# tweite.net
KiCad netlist of a schematic drawn in EAGLE
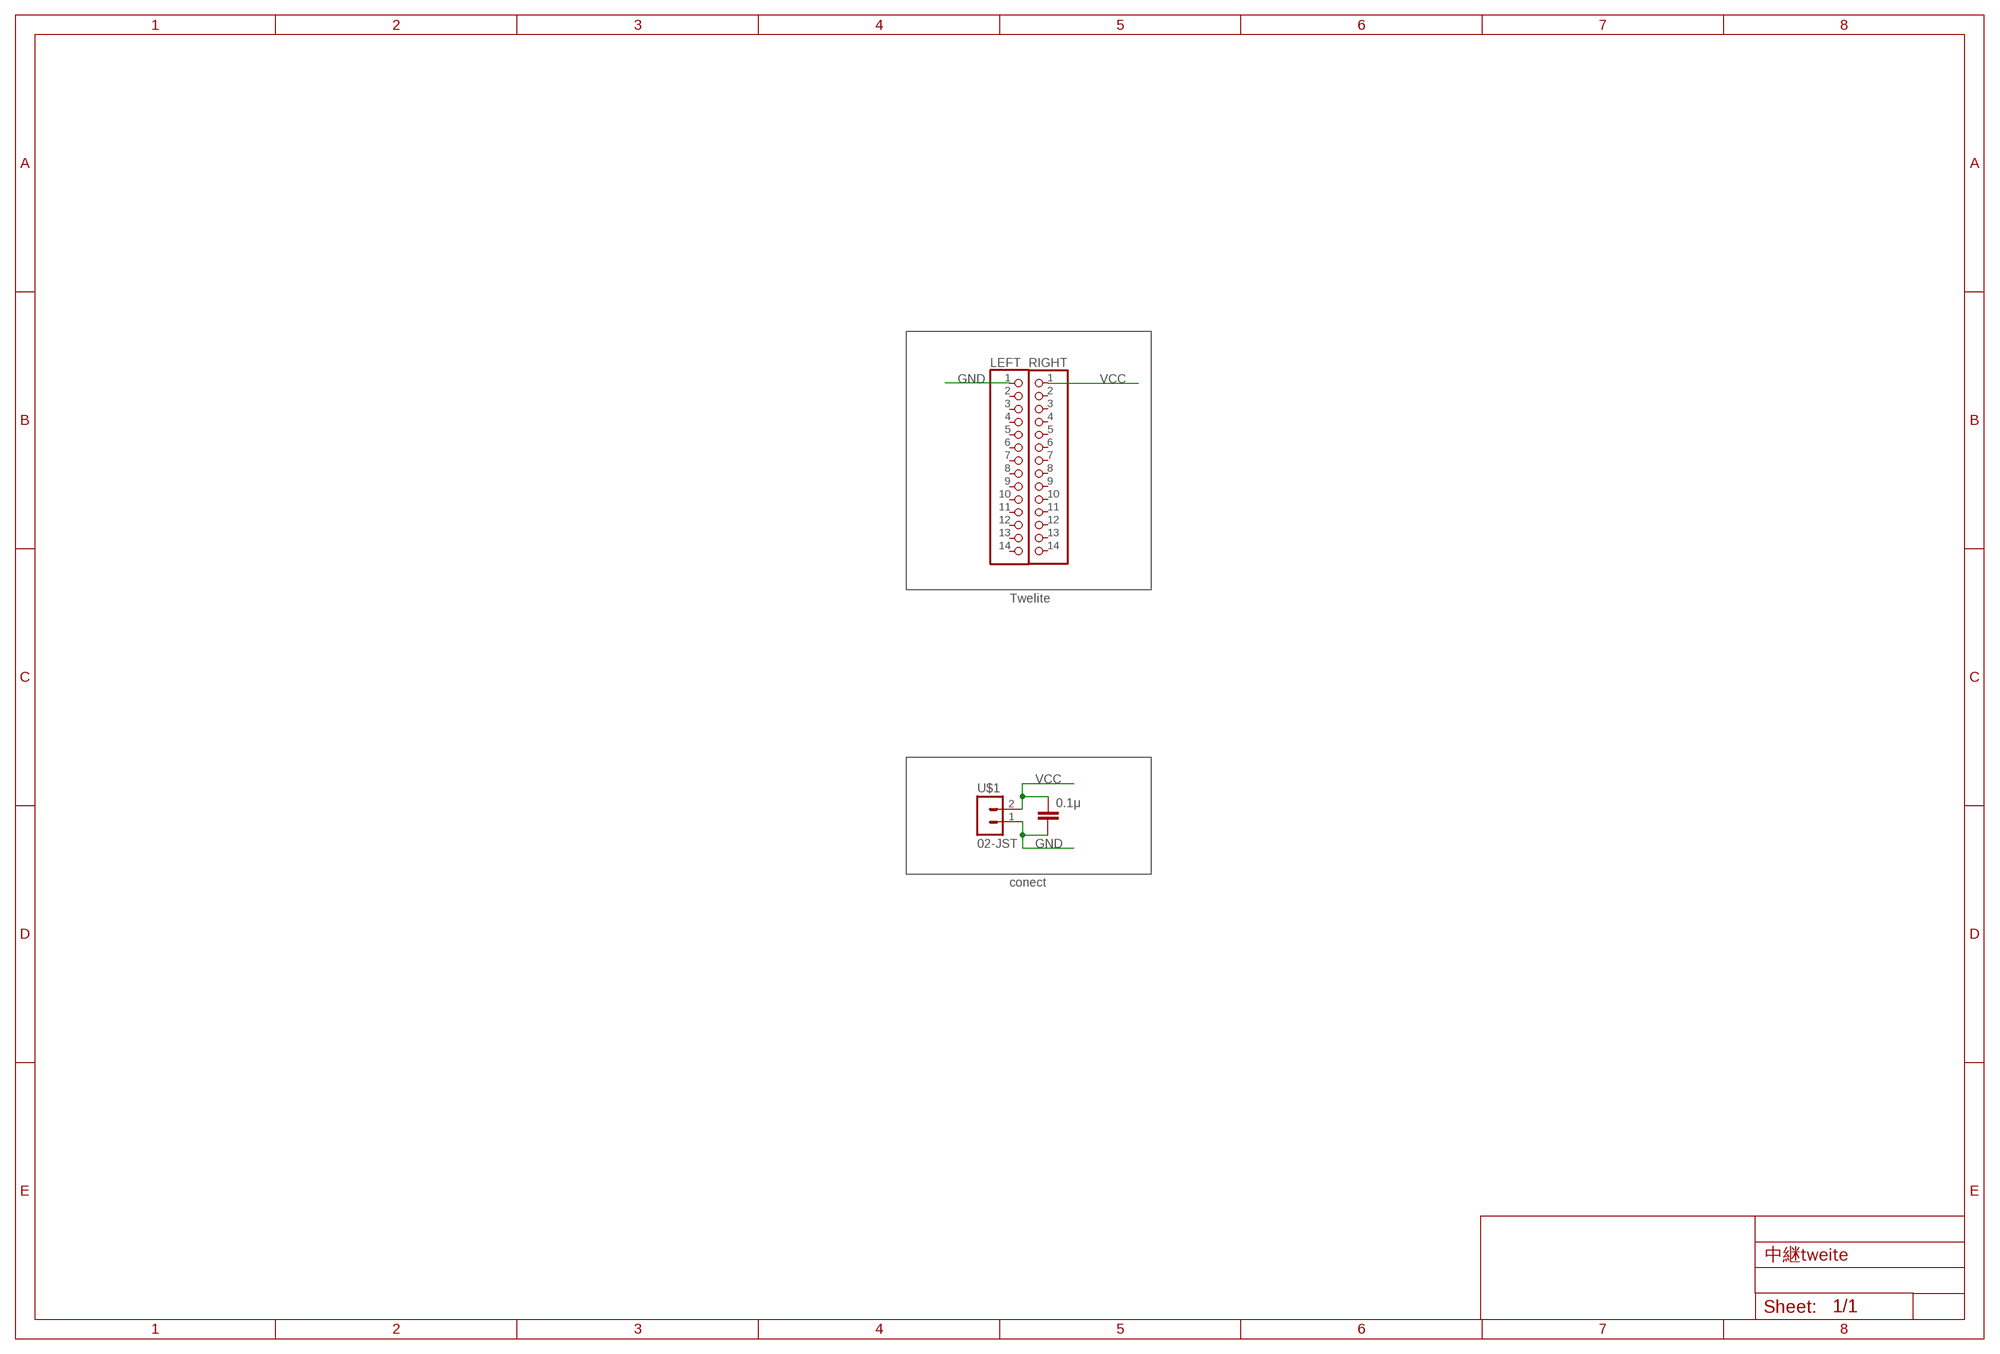
[diagram p0: schematic, sheet 1]

(export (version "E")
  (design (tool "Eeschema 10.0.6"))
  (components
    (comp (ref "0.1μ")
      (value "C-EU025-024X044")
      (footprint "eagle-import:C025-024X044")
      (libsource (lib "eagle-import") (part "C-EU025-024X044"))
    )
    (comp (ref "LEFT")
      (value "PINHD-1X14")
      (footprint "eagle-import:1X14")
      (libsource (lib "eagle-import") (part "PINHD-1X14"))
    )
    (comp (ref "RIGHT")
      (value "PINHD-1X14")
      (footprint "eagle-import:1X14")
      (libsource (lib "eagle-import") (part "PINHD-1X14"))
    )
    (comp (ref "U$1")
      (value "02-JST")
      (footprint "eagle-import:B2B-XH")
      (libsource (lib "eagle-import") (part "02-JST"))
    )
  )
  (nets
    (net (code "1") (name "/GND") (class "Default")
      (node (ref "0.1μ") (pin "2") (pinfunction "2_2") (pintype "passive"))
      (node (ref "LEFT") (pin "1") (pinfunction "1_1") (pintype "passive"))
      (node (ref "U$1") (pin "1") (pinfunction "1_1") (pintype "passive"))
    )
    (net (code "2") (name "/VCC") (class "Default")
      (node (ref "0.1μ") (pin "1") (pinfunction "1_1") (pintype "passive"))
      (node (ref "RIGHT") (pin "1") (pinfunction "1_1") (pintype "passive"))
      (node (ref "U$1") (pin "2") (pinfunction "2_2") (pintype "passive"))
    )
    (net (code "3") (name "unconnected-(LEFT-Pad2)") (class "Default")
      (node (ref "LEFT") (pin "2") (pinfunction "2_2") (pintype "passive"))
    )
    (net (code "4") (name "unconnected-(LEFT-Pad3)") (class "Default")
      (node (ref "LEFT") (pin "3") (pinfunction "3_3") (pintype "passive"))
    )
    (net (code "5") (name "unconnected-(LEFT-Pad4)") (class "Default")
      (node (ref "LEFT") (pin "4") (pinfunction "4_4") (pintype "passive"))
    )
    (net (code "6") (name "unconnected-(LEFT-Pad5)") (class "Default")
      (node (ref "LEFT") (pin "5") (pinfunction "5_5") (pintype "passive"))
    )
    (net (code "7") (name "unconnected-(LEFT-Pad6)") (class "Default")
      (node (ref "LEFT") (pin "6") (pinfunction "6_6") (pintype "passive"))
    )
    (net (code "8") (name "unconnected-(LEFT-Pad7)") (class "Default")
      (node (ref "LEFT") (pin "7") (pinfunction "7_7") (pintype "passive"))
    )
    (net (code "9") (name "unconnected-(LEFT-Pad8)") (class "Default")
      (node (ref "LEFT") (pin "8") (pinfunction "8_8") (pintype "passive"))
    )
    (net (code "10") (name "unconnected-(LEFT-Pad9)") (class "Default")
      (node (ref "LEFT") (pin "9") (pinfunction "9_9") (pintype "passive"))
    )
    (net (code "11") (name "unconnected-(LEFT-Pad10)") (class "Default")
      (node (ref "LEFT") (pin "10") (pinfunction "10_10") (pintype "passive"))
    )
    (net (code "12") (name "unconnected-(LEFT-Pad11)") (class "Default")
      (node (ref "LEFT") (pin "11") (pinfunction "11_11") (pintype "passive"))
    )
    (net (code "13") (name "unconnected-(LEFT-Pad12)") (class "Default")
      (node (ref "LEFT") (pin "12") (pinfunction "12_12") (pintype "passive"))
    )
    (net (code "14") (name "unconnected-(LEFT-Pad13)") (class "Default")
      (node (ref "LEFT") (pin "13") (pinfunction "13_13") (pintype "passive"))
    )
    (net (code "15") (name "unconnected-(LEFT-Pad14)") (class "Default")
      (node (ref "LEFT") (pin "14") (pinfunction "14_14") (pintype "passive"))
    )
    (net (code "16") (name "unconnected-(RIGHT-Pad2)") (class "Default")
      (node (ref "RIGHT") (pin "2") (pinfunction "2_2") (pintype "passive"))
    )
    (net (code "17") (name "unconnected-(RIGHT-Pad3)") (class "Default")
      (node (ref "RIGHT") (pin "3") (pinfunction "3_3") (pintype "passive"))
    )
    (net (code "18") (name "unconnected-(RIGHT-Pad4)") (class "Default")
      (node (ref "RIGHT") (pin "4") (pinfunction "4_4") (pintype "passive"))
    )
    (net (code "19") (name "unconnected-(RIGHT-Pad5)") (class "Default")
      (node (ref "RIGHT") (pin "5") (pinfunction "5_5") (pintype "passive"))
    )
    (net (code "20") (name "unconnected-(RIGHT-Pad6)") (class "Default")
      (node (ref "RIGHT") (pin "6") (pinfunction "6_6") (pintype "passive"))
    )
    (net (code "21") (name "unconnected-(RIGHT-Pad7)") (class "Default")
      (node (ref "RIGHT") (pin "7") (pinfunction "7_7") (pintype "passive"))
    )
    (net (code "22") (name "unconnected-(RIGHT-Pad8)") (class "Default")
      (node (ref "RIGHT") (pin "8") (pinfunction "8_8") (pintype "passive"))
    )
    (net (code "23") (name "unconnected-(RIGHT-Pad9)") (class "Default")
      (node (ref "RIGHT") (pin "9") (pinfunction "9_9") (pintype "passive"))
    )
    (net (code "24") (name "unconnected-(RIGHT-Pad10)") (class "Default")
      (node (ref "RIGHT") (pin "10") (pinfunction "10_10") (pintype "passive"))
    )
    (net (code "25") (name "unconnected-(RIGHT-Pad11)") (class "Default")
      (node (ref "RIGHT") (pin "11") (pinfunction "11_11") (pintype "passive"))
    )
    (net (code "26") (name "unconnected-(RIGHT-Pad12)") (class "Default")
      (node (ref "RIGHT") (pin "12") (pinfunction "12_12") (pintype "passive"))
    )
    (net (code "27") (name "unconnected-(RIGHT-Pad13)") (class "Default")
      (node (ref "RIGHT") (pin "13") (pinfunction "13_13") (pintype "passive"))
    )
    (net (code "28") (name "unconnected-(RIGHT-Pad14)") (class "Default")
      (node (ref "RIGHT") (pin "14") (pinfunction "14_14") (pintype "passive"))
    )
  )
)
